# PROIECT_OPEN_READER_v57.net
KiCad netlist of a schematic drawn in EAGLE
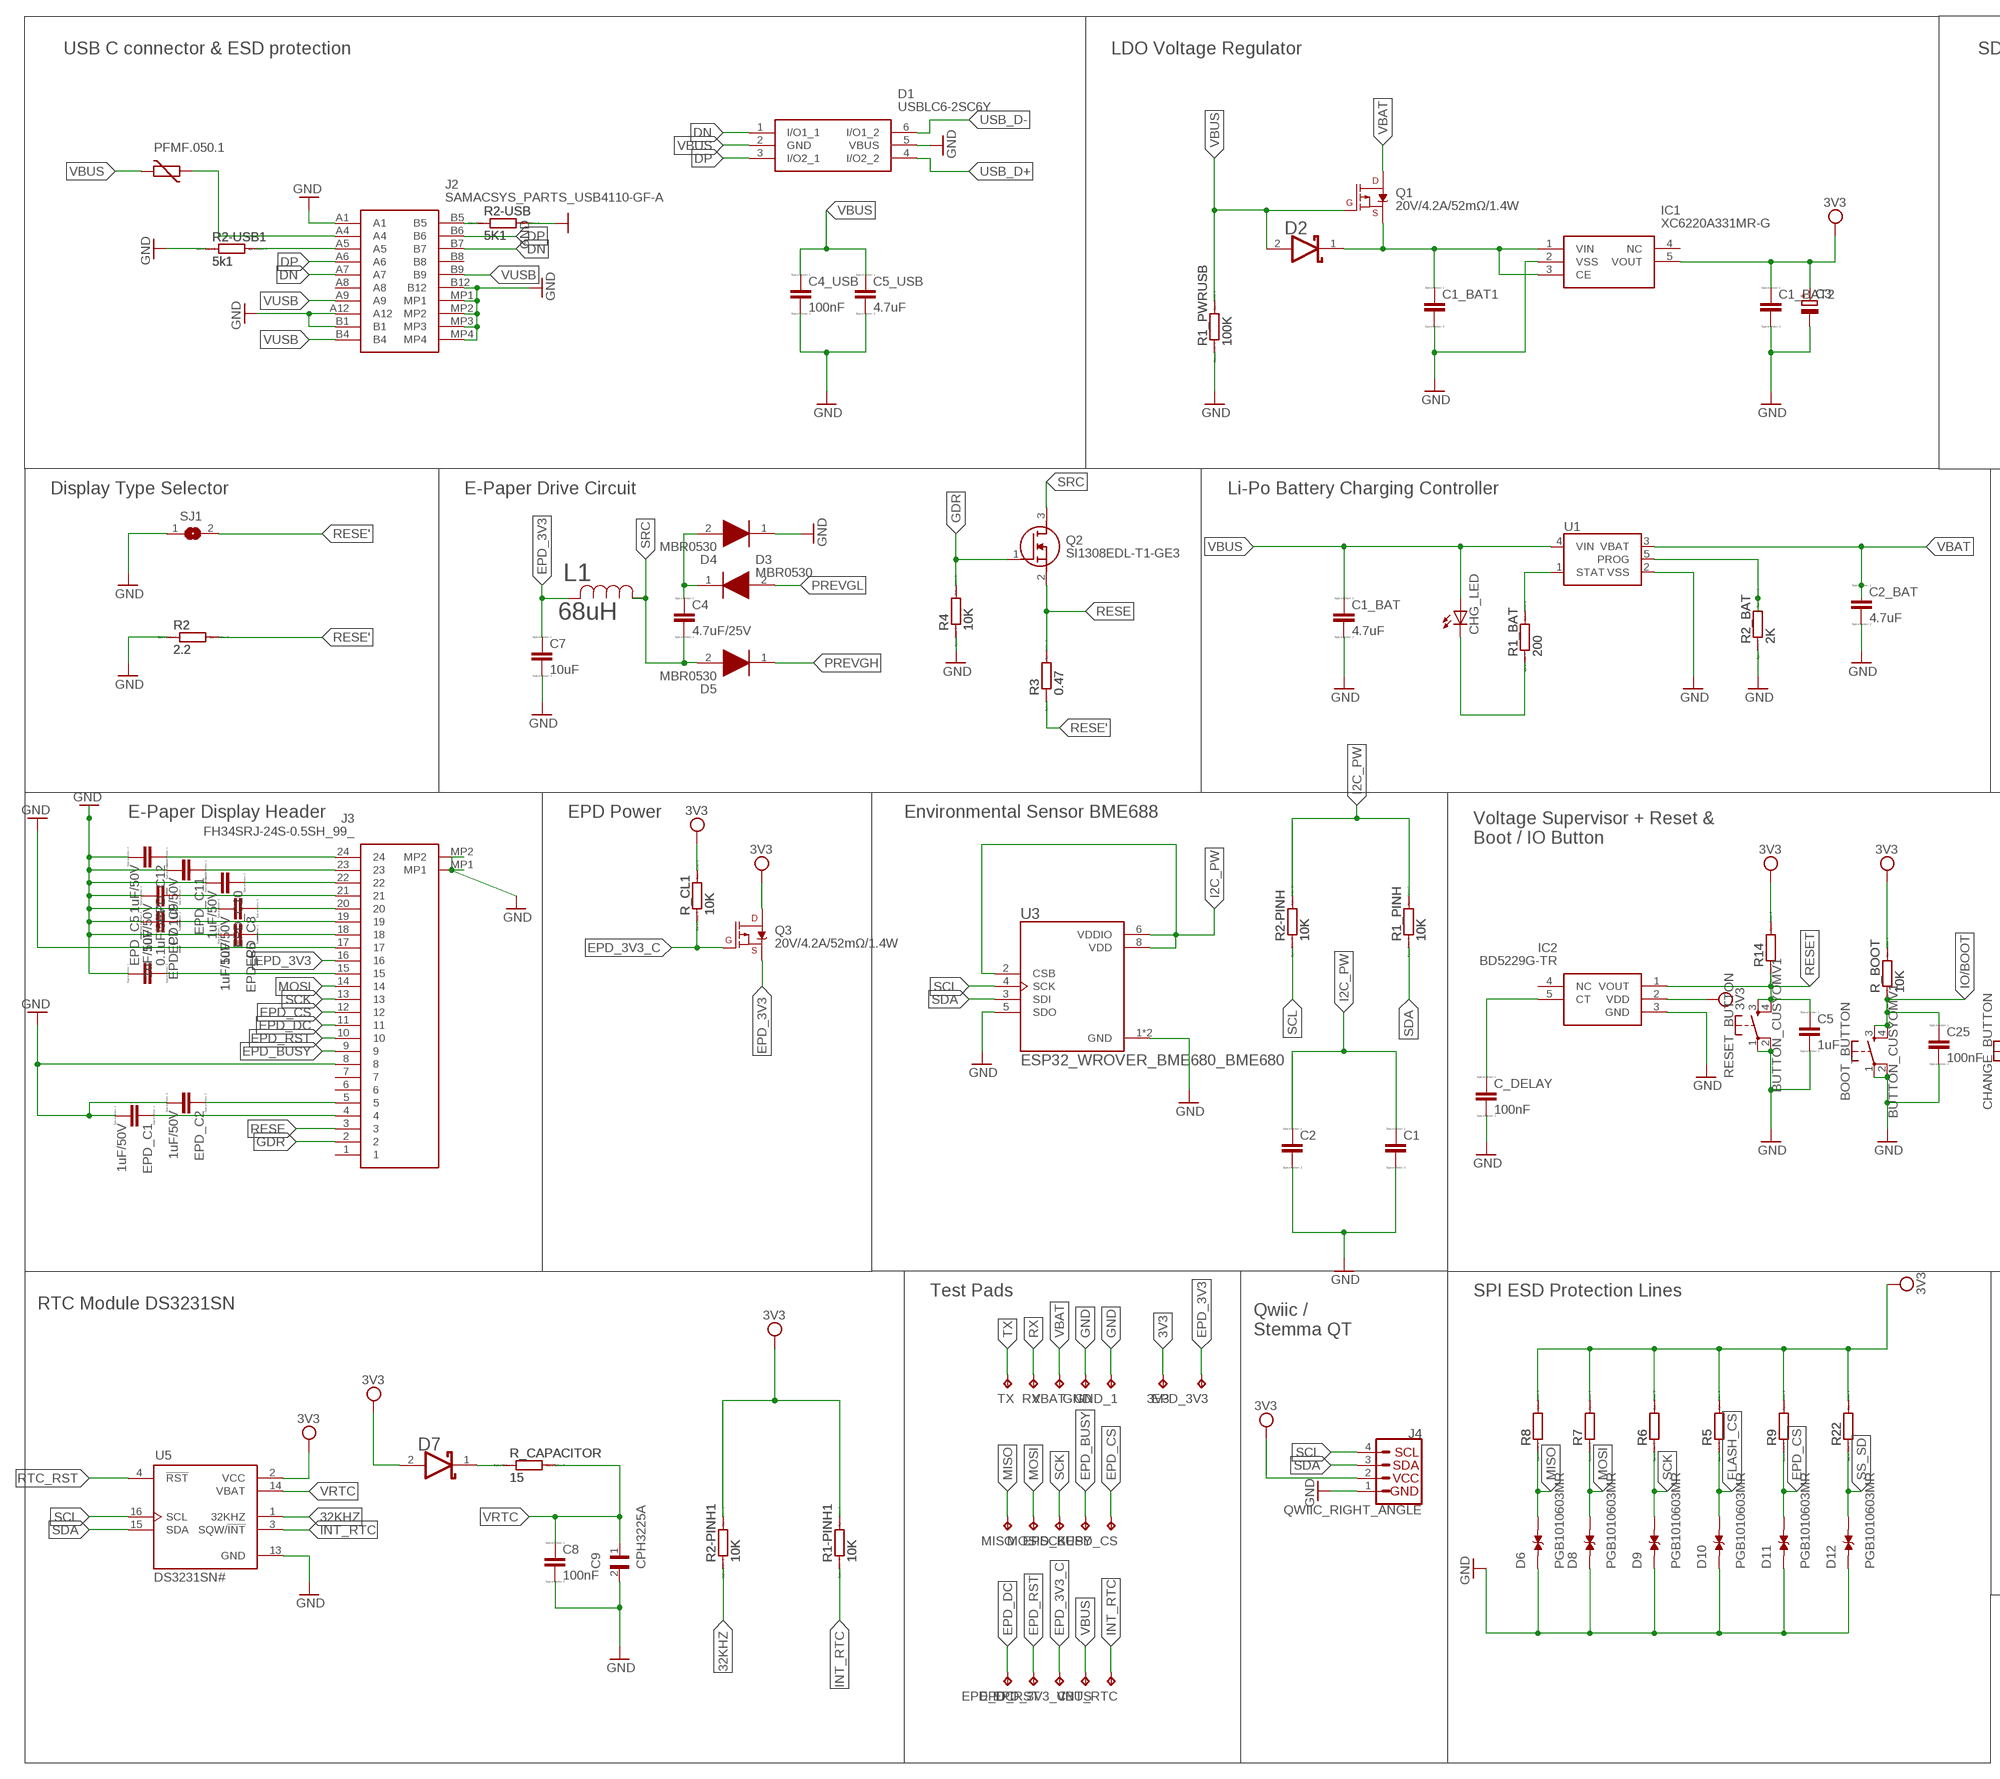
[diagram p0: schematic, sheet 1, part 1 of 2]
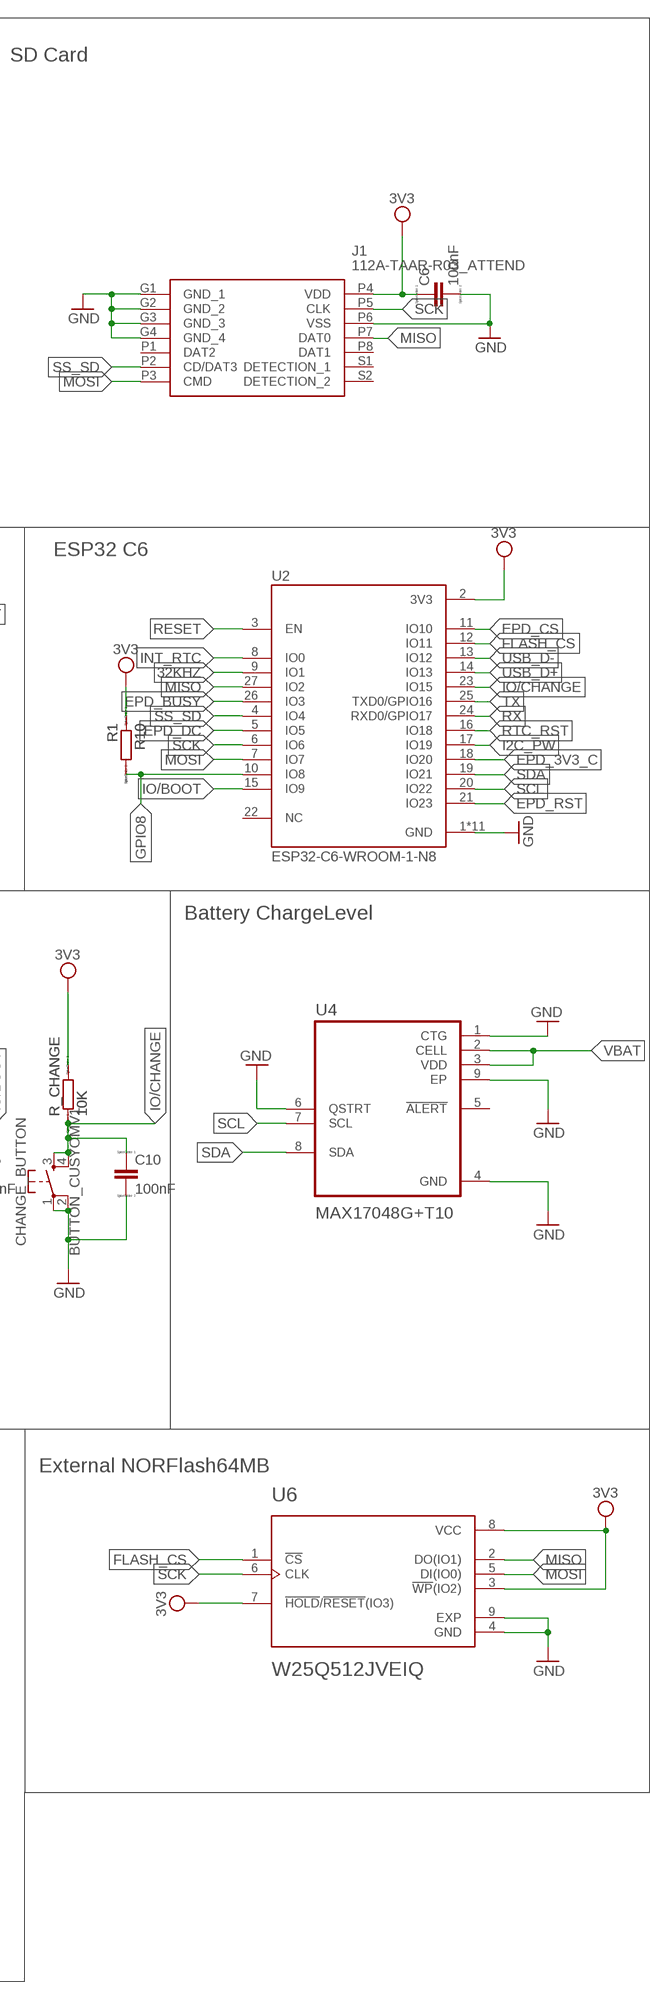
[diagram p1: schematic, sheet 1, part 2 of 2]

(export (version "E")
  (design (tool "Eeschema 10.0.6"))
  (components
    (comp (ref "3V3")
      (value "TPTP20R")
      (footprint "eagle-import:TP20R")
      (libsource (lib "eagle-import") (part "TPTP20R"))
    )
    (comp (ref "BOOT_BUTTON")
      (value "BUTTON_CUSYOMV1")
      (footprint "eagle-import:MYBUTTON")
      (libsource (lib "eagle-import") (part "BUTTON_CUSYOMV1"))
    )
    (comp (ref "C1")
      (value "EAGLE-LTSPICE_CC0402")
      (footprint "eagle-import:EAGLE-LTSPICE_C0402")
      (libsource (lib "eagle-import") (part "EAGLE-LTSPICE_CC0402"))
    )
    (comp (ref "C1_BAT")
      (value "4.7uF")
      (footprint "eagle-import:EAGLE-LTSPICE_C0402")
      (libsource (lib "eagle-import") (part "EAGLE-LTSPICE_CC0402"))
    )
    (comp (ref "C1_BAT1")
      (value "EAGLE-LTSPICE_CC0402")
      (footprint "eagle-import:EAGLE-LTSPICE_C0402")
      (libsource (lib "eagle-import") (part "EAGLE-LTSPICE_CC0402"))
    )
    (comp (ref "C1_BAT2")
      (value "EAGLE-LTSPICE_CC0402")
      (footprint "eagle-import:EAGLE-LTSPICE_C0402")
      (libsource (lib "eagle-import") (part "EAGLE-LTSPICE_CC0402"))
    )
    (comp (ref "C2")
      (value "EAGLE-LTSPICE_CC0402")
      (footprint "eagle-import:EAGLE-LTSPICE_C0402")
      (libsource (lib "eagle-import") (part "EAGLE-LTSPICE_CC0402"))
    )
    (comp (ref "C2_BAT")
      (value "4.7uF")
      (footprint "eagle-import:EAGLE-LTSPICE_C0402")
      (libsource (lib "eagle-import") (part "EAGLE-LTSPICE_CC0402"))
    )
    (comp (ref "C3")
      (value "RCL_CPOL-EUCT3528")
      (footprint "eagle-import:RCL_CT3528")
      (libsource (lib "eagle-import") (part "RCL_CPOL-EUCT3528"))
    )
    (comp (ref "C4")
      (value "4.7uF/25V")
      (footprint "eagle-import:EAGLE-LTSPICE_C0402")
      (libsource (lib "eagle-import") (part "EAGLE-LTSPICE_CC0402"))
    )
    (comp (ref "C4_USB")
      (value "100nF")
      (footprint "eagle-import:EAGLE-LTSPICE_C0402")
      (libsource (lib "eagle-import") (part "EAGLE-LTSPICE_CC0402"))
    )
    (comp (ref "C5")
      (value "1uF")
      (footprint "eagle-import:EAGLE-LTSPICE_C0402")
      (libsource (lib "eagle-import") (part "EAGLE-LTSPICE_CC0402"))
    )
    (comp (ref "C5_USB")
      (value "4.7uF")
      (footprint "eagle-import:EAGLE-LTSPICE_C0402")
      (libsource (lib "eagle-import") (part "EAGLE-LTSPICE_CC0402"))
    )
    (comp (ref "C6")
      (value "100nF")
      (footprint "eagle-import:EAGLE-LTSPICE_C0402")
      (libsource (lib "eagle-import") (part "EAGLE-LTSPICE_CC0402"))
    )
    (comp (ref "C7")
      (value "10uF")
      (footprint "eagle-import:EAGLE-LTSPICE_C0402")
      (libsource (lib "eagle-import") (part "EAGLE-LTSPICE_CC0402"))
    )
    (comp (ref "C8")
      (value "100nF")
      (footprint "eagle-import:EAGLE-LTSPICE_C0402")
      (libsource (lib "eagle-import") (part "EAGLE-LTSPICE_CC0402"))
    )
    (comp (ref "C9")
      (value "CPH3225A")
      (footprint "eagle-import:CAPCP3225X100N")
      (fields (field (name "MF") "Seiko Instruments"))
      (libsource (lib "eagle-import") (part "CPH3225A"))
    )
    (comp (ref "C10")
      (value "100nF")
      (footprint "eagle-import:EAGLE-LTSPICE_C0402")
      (libsource (lib "eagle-import") (part "EAGLE-LTSPICE_CC0402"))
    )
    (comp (ref "C25")
      (value "100nF")
      (footprint "eagle-import:EAGLE-LTSPICE_C0402")
      (libsource (lib "eagle-import") (part "EAGLE-LTSPICE_CC0402"))
    )
    (comp (ref "CHANGE_BUTTON")
      (value "BUTTON_CUSYOMV1")
      (footprint "eagle-import:MYBUTTON")
      (libsource (lib "eagle-import") (part "BUTTON_CUSYOMV1"))
    )
    (comp (ref "CHG_LED")
      (value "ADAFRUIT_LEDCHIP-LED0603")
      (footprint "eagle-import:ADAFRUIT_CHIP-LED0603")
      (libsource (lib "eagle-import") (part "ADAFRUIT_LEDCHIP-LED0603"))
    )
    (comp (ref "C_DELAY")
      (value "100nF")
      (footprint "eagle-import:EAGLE-LTSPICE_C0402")
      (libsource (lib "eagle-import") (part "EAGLE-LTSPICE_CC0402"))
    )
    (comp (ref "D1")
      (value "USBLC6-2SC6Y")
      (footprint "eagle-import:SOT95P280X145-6N")
      (fields (field (name "MF") "STMicroelectronics"))
      (libsource (lib "eagle-import") (part "USBLC6-2SC6Y"))
    )
    (comp (ref "D2")
      (value "ESP32_WROVER_AVX---SD0805S020S1R0_AVX_SD0805S020S1R0_0_0AVX_SD0805S020S1R0_0_0")
      (footprint "eagle-import:ESP32_WROVER_AVX---SD0805S020S1R0_AVX_SD0805S020S1R0_0")
      (fields
        (field (name "DIGIKEY_PART_NUMBER") "478-7800-1-ND")
        (field (name "MF") "AVX")
        (field (name "MOUSER_PART_NUMBER") "581-SD0805S020S1R0")
      )
      (libsource (lib "eagle-import") (part "ESP32_WROVER_AVX---SD0805S020S1R0_AVX_SD0805S020S1R0_0_0AVX_SD0805S020S1R0_0_0"))
    )
    (comp (ref "D3")
      (value "MBR0530")
      (footprint "eagle-import:SOD3716X135N")
      (fields (field (name "MF") "ON Semiconductor"))
      (libsource (lib "eagle-import") (part "MBR0530"))
    )
    (comp (ref "D4")
      (value "MBR0530")
      (footprint "eagle-import:SOD3716X135N")
      (fields (field (name "MF") "ON Semiconductor"))
      (libsource (lib "eagle-import") (part "MBR0530"))
    )
    (comp (ref "D5")
      (value "MBR0530")
      (footprint "eagle-import:SOD3716X135N")
      (fields (field (name "MF") "ON Semiconductor"))
      (libsource (lib "eagle-import") (part "MBR0530"))
    )
    (comp (ref "D6")
      (value "PGB1010603MR")
      (footprint "eagle-import:DIOC1608X36N")
      (fields (field (name "MF") "Littelfuse Inc."))
      (libsource (lib "eagle-import") (part "PGB1010603MR"))
    )
    (comp (ref "D7")
      (value "ESP32_WROVER_AVX---SD0805S020S1R0_AVX_SD0805S020S1R0_0_0AVX_SD0805S020S1R0_0_0")
      (footprint "eagle-import:ESP32_WROVER_AVX---SD0805S020S1R0_AVX_SD0805S020S1R0_0")
      (fields
        (field (name "DIGIKEY_PART_NUMBER") "478-7800-1-ND")
        (field (name "MF") "AVX")
        (field (name "MOUSER_PART_NUMBER") "581-SD0805S020S1R0")
      )
      (libsource (lib "eagle-import") (part "ESP32_WROVER_AVX---SD0805S020S1R0_AVX_SD0805S020S1R0_0_0AVX_SD0805S020S1R0_0_0"))
    )
    (comp (ref "D8")
      (value "PGB1010603MR")
      (footprint "eagle-import:DIOC1608X36N")
      (fields (field (name "MF") "Littelfuse Inc."))
      (libsource (lib "eagle-import") (part "PGB1010603MR"))
    )
    (comp (ref "D9")
      (value "PGB1010603MR")
      (footprint "eagle-import:DIOC1608X36N")
      (fields (field (name "MF") "Littelfuse Inc."))
      (libsource (lib "eagle-import") (part "PGB1010603MR"))
    )
    (comp (ref "D10")
      (value "PGB1010603MR")
      (footprint "eagle-import:DIOC1608X36N")
      (fields (field (name "MF") "Littelfuse Inc."))
      (libsource (lib "eagle-import") (part "PGB1010603MR"))
    )
    (comp (ref "D11")
      (value "PGB1010603MR")
      (footprint "eagle-import:DIOC1608X36N")
      (fields (field (name "MF") "Littelfuse Inc."))
      (libsource (lib "eagle-import") (part "PGB1010603MR"))
    )
    (comp (ref "D12")
      (value "PGB1010603MR")
      (footprint "eagle-import:DIOC1608X36N")
      (fields (field (name "MF") "Littelfuse Inc."))
      (libsource (lib "eagle-import") (part "PGB1010603MR"))
    )
    (comp (ref "EPD_3V3")
      (value "TPTP20R")
      (footprint "eagle-import:TP20R")
      (libsource (lib "eagle-import") (part "TPTP20R"))
    )
    (comp (ref "EPD_3V3_C")
      (value "TPTP20R")
      (footprint "eagle-import:TP20R")
      (libsource (lib "eagle-import") (part "TPTP20R"))
    )
    (comp (ref "EPD_BUSY")
      (value "TPTP20R")
      (footprint "eagle-import:TP20R")
      (libsource (lib "eagle-import") (part "TPTP20R"))
    )
    (comp (ref "EPD_C1")
      (value "1uF/50V")
      (footprint "eagle-import:EAGLE-LTSPICE_C0402")
      (libsource (lib "eagle-import") (part "EAGLE-LTSPICE_CC0402"))
    )
    (comp (ref "EPD_C2")
      (value "1uF/50V")
      (footprint "eagle-import:EAGLE-LTSPICE_C0402")
      (libsource (lib "eagle-import") (part "EAGLE-LTSPICE_CC0402"))
    )
    (comp (ref "EPD_C5")
      (value "0.1uF/50V")
      (footprint "eagle-import:EAGLE-LTSPICE_C0402")
      (libsource (lib "eagle-import") (part "EAGLE-LTSPICE_CC0402"))
    )
    (comp (ref "EPD_C6")
      (value "1uF/50V")
      (footprint "eagle-import:EAGLE-LTSPICE_C0402")
      (libsource (lib "eagle-import") (part "EAGLE-LTSPICE_CC0402"))
    )
    (comp (ref "EPD_C7")
      (value "1uF/50V")
      (footprint "eagle-import:EAGLE-LTSPICE_C0402")
      (libsource (lib "eagle-import") (part "EAGLE-LTSPICE_CC0402"))
    )
    (comp (ref "EPD_C8")
      (value "1uF/50V")
      (footprint "eagle-import:EAGLE-LTSPICE_C0402")
      (libsource (lib "eagle-import") (part "EAGLE-LTSPICE_CC0402"))
    )
    (comp (ref "EPD_C9")
      (value "1uF/50V")
      (footprint "eagle-import:EAGLE-LTSPICE_C0402")
      (libsource (lib "eagle-import") (part "EAGLE-LTSPICE_CC0402"))
    )
    (comp (ref "EPD_C10")
      (value "1uF/50V")
      (footprint "eagle-import:EAGLE-LTSPICE_C0402")
      (libsource (lib "eagle-import") (part "EAGLE-LTSPICE_CC0402"))
    )
    (comp (ref "EPD_C11")
      (value "1uF/50V")
      (footprint "eagle-import:EAGLE-LTSPICE_C0402")
      (libsource (lib "eagle-import") (part "EAGLE-LTSPICE_CC0402"))
    )
    (comp (ref "EPD_C12")
      (value "1uF/50V")
      (footprint "eagle-import:EAGLE-LTSPICE_C0402")
      (libsource (lib "eagle-import") (part "EAGLE-LTSPICE_CC0402"))
    )
    (comp (ref "EPD_CS")
      (value "TPTP20R")
      (footprint "eagle-import:TP20R")
      (libsource (lib "eagle-import") (part "TPTP20R"))
    )
    (comp (ref "EPD_DC")
      (value "TPTP20R")
      (footprint "eagle-import:TP20R")
      (libsource (lib "eagle-import") (part "TPTP20R"))
    )
    (comp (ref "EPD_RST")
      (value "TPTP20R")
      (footprint "eagle-import:TP20R")
      (libsource (lib "eagle-import") (part "TPTP20R"))
    )
    (comp (ref "GND")
      (value "TPTP20R")
      (footprint "eagle-import:TP20R")
      (libsource (lib "eagle-import") (part "TPTP20R"))
    )
    (comp (ref "GND_1")
      (value "TPTP20R")
      (footprint "eagle-import:TP20R")
      (libsource (lib "eagle-import") (part "TPTP20R"))
    )
    (comp (ref "IC1")
      (value "XC6220A331MR-G")
      (footprint "eagle-import:SOT95P280X120-5N")
      (fields (field (name "MOUSER_PART_NUMBER") "865-XC6220A331MR-G"))
      (libsource (lib "eagle-import") (part "XC6220A331MR-G"))
    )
    (comp (ref "IC2")
      (value "BD5229G-TR")
      (footprint "eagle-import:SOT95P280X125-5N")
      (fields (field (name "MOUSER_PART_NUMBER") "755-BD5229G-TR"))
      (libsource (lib "eagle-import") (part "BD5229G-TR"))
    )
    (comp (ref "INT_RTC")
      (value "TPTP20R")
      (footprint "eagle-import:TP20R")
      (libsource (lib "eagle-import") (part "TPTP20R"))
    )
    (comp (ref "J1")
      (value "112A-TAAR-R03_ATTEND")
      (footprint "eagle-import:112ATAARR03ATTEND")
      (fields (field (name "MANUFACTURER_PART_NUMBER") "112A-TAAR-R03 ATTEND"))
      (libsource (lib "eagle-import") (part "112A-TAAR-R03_ATTEND"))
    )
    (comp (ref "J2")
      (value "SAMACSYS_PARTS_USB4110-GF-A")
      (footprint "eagle-import:SAMACSYS_PARTS_USB4110GFA")
      (fields
        (field (name "MANUFACTURER_PART_NUMBER") "USB4110-GF-A")
        (field (name "MOUSER_PART_NUMBER") "640-USB4110-GF-A")
      )
      (libsource (lib "eagle-import") (part "SAMACSYS_PARTS_USB4110-GF-A"))
    )
    (comp (ref "J3")
      (value "FH34SRJ-24S-0.5SH_99_")
      (footprint "eagle-import:FH34SRJ24S05SH99")
      (fields
        (field (name "MANUFACTURER_PART_NUMBER") "FH34SRJ-24S-0.5SH(99)")
        (field (name "MOUSER_PART_NUMBER") "798-FH34SRJ24S05SH99")
      )
      (libsource (lib "eagle-import") (part "FH34SRJ-24S-0.5SH_99_"))
    )
    (comp (ref "J4")
      (value "QWIIC_RIGHT_ANGLE")
      (footprint "eagle-import:JST04_1MM_RA")
      (libsource (lib "eagle-import") (part "QWIIC_CONNECTORJS-1MM"))
    )
    (comp (ref "L1")
      (value "68uH")
      (footprint "eagle-import:IND_4828-WE-TPC_WRE")
      (fields
        (field (name "MANUFACTURER_PART_NUMBER") "744043680")
        (field (name "COPYRIGHT") "Copyright (C) 2024 Ultra Librarian. All rights reserved.")
      )
      (libsource (lib "eagle-import") (part "744043680IND_4828-WE-TPC_WRE"))
    )
    (comp (ref "MISO")
      (value "TPTP20R")
      (footprint "eagle-import:TP20R")
      (libsource (lib "eagle-import") (part "TPTP20R"))
    )
    (comp (ref "MOSI")
      (value "TPTP20R")
      (footprint "eagle-import:TP20R")
      (libsource (lib "eagle-import") (part "TPTP20R"))
    )
    (comp (ref "PFMF.050.1")
      (value "ESP32C6_VARISTORCN1812")
      (footprint "eagle-import:ESP32C6_VARISTOR_CT_CN1812")
      (libsource (lib "eagle-import") (part "ESP32C6_VARISTORCN1812"))
    )
    (comp (ref "Q1")
      (value "20V/4.2A/52mΩ/1.4W")
      (footprint "eagle-import:ESP32_WROVER_SPARKFUN-DISCRETESEMI_SOT23-3")
      (libsource (lib "eagle-import") (part "ESP32_WROVER_SPARKFUN-DISCRETESEMI_MOSFET_PCH-DMG2305UX-7"))
    )
    (comp (ref "Q2")
      (value "SI1308EDL-T1-GE3")
      (footprint "eagle-import:SOT65P210X110-3N")
      (fields (field (name "MF") "Vishay Siliconix"))
      (libsource (lib "eagle-import") (part "SI1308EDL-T1-GE3"))
    )
    (comp (ref "Q3")
      (value "20V/4.2A/52mΩ/1.4W")
      (footprint "eagle-import:ESP32_WROVER_SPARKFUN-DISCRETESEMI_SOT23-3")
      (libsource (lib "eagle-import") (part "ESP32_WROVER_SPARKFUN-DISCRETESEMI_MOSFET_PCH-DMG2305UX-7"))
    )
    (comp (ref "R1-PINH1")
      (value "10K")
      (footprint "eagle-import:ESP32_WROVER_EAGLE-LTSPICE_R0402")
      (libsource (lib "eagle-import") (part "ESP32_WROVER_EAGLE-LTSPICE_RR0402"))
    )
    (comp (ref "R1_BAT")
      (value "200")
      (footprint "eagle-import:ESP32_WROVER_EAGLE-LTSPICE_R0402")
      (libsource (lib "eagle-import") (part "ESP32_WROVER_EAGLE-LTSPICE_RR0402"))
    )
    (comp (ref "R1_PINH")
      (value "10K")
      (footprint "eagle-import:ESP32_WROVER_EAGLE-LTSPICE_R0402")
      (libsource (lib "eagle-import") (part "ESP32_WROVER_EAGLE-LTSPICE_RR0402"))
    )
    (comp (ref "R1_PWRUSB")
      (value "100K")
      (footprint "eagle-import:ESP32_WROVER_EAGLE-LTSPICE_R0402")
      (libsource (lib "eagle-import") (part "ESP32_WROVER_EAGLE-LTSPICE_RR0402"))
    )
    (comp (ref "R2")
      (value "2.2")
      (footprint "eagle-import:ESP32_WROVER_EAGLE-LTSPICE_R0402")
      (libsource (lib "eagle-import") (part "ESP32_WROVER_EAGLE-LTSPICE_RR0402"))
    )
    (comp (ref "R2-PINH")
      (value "10K")
      (footprint "eagle-import:ESP32_WROVER_EAGLE-LTSPICE_R0402")
      (libsource (lib "eagle-import") (part "ESP32_WROVER_EAGLE-LTSPICE_RR0402"))
    )
    (comp (ref "R2-PINH1")
      (value "10K")
      (footprint "eagle-import:ESP32_WROVER_EAGLE-LTSPICE_R0402")
      (libsource (lib "eagle-import") (part "ESP32_WROVER_EAGLE-LTSPICE_RR0402"))
    )
    (comp (ref "R2-USB")
      (value "5K1")
      (footprint "eagle-import:ESP32_WROVER_EAGLE-LTSPICE_R0402")
      (libsource (lib "eagle-import") (part "ESP32_WROVER_EAGLE-LTSPICE_RR0402"))
    )
    (comp (ref "R2-USB1")
      (value "5k1")
      (footprint "eagle-import:ESP32_WROVER_EAGLE-LTSPICE_R0402")
      (libsource (lib "eagle-import") (part "ESP32_WROVER_EAGLE-LTSPICE_RR0402"))
    )
    (comp (ref "R2_BAT")
      (value "2K")
      (footprint "eagle-import:ESP32_WROVER_EAGLE-LTSPICE_R0402")
      (libsource (lib "eagle-import") (part "ESP32_WROVER_EAGLE-LTSPICE_RR0402"))
    )
    (comp (ref "R3")
      (value "0.47")
      (footprint "eagle-import:ESP32_WROVER_EAGLE-LTSPICE_R0402")
      (libsource (lib "eagle-import") (part "ESP32_WROVER_EAGLE-LTSPICE_RR0402"))
    )
    (comp (ref "R4")
      (value "10K")
      (footprint "eagle-import:ESP32_WROVER_EAGLE-LTSPICE_R0402")
      (libsource (lib "eagle-import") (part "ESP32_WROVER_EAGLE-LTSPICE_RR0402"))
    )
    (comp (ref "R5")
      (value "ESP32_WROVER_EAGLE-LTSPICE_RR0402")
      (footprint "eagle-import:ESP32_WROVER_EAGLE-LTSPICE_R0402")
      (libsource (lib "eagle-import") (part "ESP32_WROVER_EAGLE-LTSPICE_RR0402"))
    )
    (comp (ref "R6")
      (value "ESP32_WROVER_EAGLE-LTSPICE_RR0402")
      (footprint "eagle-import:ESP32_WROVER_EAGLE-LTSPICE_R0402")
      (libsource (lib "eagle-import") (part "ESP32_WROVER_EAGLE-LTSPICE_RR0402"))
    )
    (comp (ref "R7")
      (value "ESP32_WROVER_EAGLE-LTSPICE_RR0402")
      (footprint "eagle-import:ESP32_WROVER_EAGLE-LTSPICE_R0402")
      (libsource (lib "eagle-import") (part "ESP32_WROVER_EAGLE-LTSPICE_RR0402"))
    )
    (comp (ref "R8")
      (value "ESP32_WROVER_EAGLE-LTSPICE_RR0402")
      (footprint "eagle-import:ESP32_WROVER_EAGLE-LTSPICE_R0402")
      (libsource (lib "eagle-import") (part "ESP32_WROVER_EAGLE-LTSPICE_RR0402"))
    )
    (comp (ref "R9")
      (value "ESP32_WROVER_EAGLE-LTSPICE_RR0402")
      (footprint "eagle-import:ESP32_WROVER_EAGLE-LTSPICE_R0402")
      (libsource (lib "eagle-import") (part "ESP32_WROVER_EAGLE-LTSPICE_RR0402"))
    )
    (comp (ref "R10")
      (value "R1")
      (footprint "eagle-import:ESP32_WROVER_EAGLE-LTSPICE_R0402")
      (libsource (lib "eagle-import") (part "ESP32_WROVER_EAGLE-LTSPICE_RR0402"))
    )
    (comp (ref "R14")
      (value "ESP32_WROVER_EAGLE-LTSPICE_RR0402")
      (footprint "eagle-import:ESP32_WROVER_EAGLE-LTSPICE_R0402")
      (libsource (lib "eagle-import") (part "ESP32_WROVER_EAGLE-LTSPICE_RR0402"))
    )
    (comp (ref "R22")
      (value "ESP32_WROVER_EAGLE-LTSPICE_RR0402")
      (footprint "eagle-import:ESP32_WROVER_EAGLE-LTSPICE_R0402")
      (libsource (lib "eagle-import") (part "ESP32_WROVER_EAGLE-LTSPICE_RR0402"))
    )
    (comp (ref "RESET_BUTTON")
      (value "BUTTON_CUSYOMV1")
      (footprint "eagle-import:MYBUTTON")
      (libsource (lib "eagle-import") (part "BUTTON_CUSYOMV1"))
    )
    (comp (ref "RX")
      (value "TPTP20R")
      (footprint "eagle-import:TP20R")
      (libsource (lib "eagle-import") (part "TPTP20R"))
    )
    (comp (ref "R_BOOT")
      (value "10K")
      (footprint "eagle-import:ESP32_WROVER_EAGLE-LTSPICE_R0402")
      (libsource (lib "eagle-import") (part "ESP32_WROVER_EAGLE-LTSPICE_RR0402"))
    )
    (comp (ref "R_CAPACITOR")
      (value "15")
      (footprint "eagle-import:ESP32_WROVER_EAGLE-LTSPICE_R0402")
      (libsource (lib "eagle-import") (part "ESP32_WROVER_EAGLE-LTSPICE_RR0402"))
    )
    (comp (ref "R_CHANGE")
      (value "10K")
      (footprint "eagle-import:ESP32_WROVER_EAGLE-LTSPICE_R0402")
      (libsource (lib "eagle-import") (part "ESP32_WROVER_EAGLE-LTSPICE_RR0402"))
    )
    (comp (ref "R_CL1")
      (value "10K")
      (footprint "eagle-import:ESP32_WROVER_EAGLE-LTSPICE_R0402")
      (libsource (lib "eagle-import") (part "ESP32_WROVER_EAGLE-LTSPICE_RR0402"))
    )
    (comp (ref "SCK")
      (value "TPTP20R")
      (footprint "eagle-import:TP20R")
      (libsource (lib "eagle-import") (part "TPTP20R"))
    )
    (comp (ref "SJ1") (value "SJ") (footprint "eagle-import:SJ") (libsource (lib "eagle-import") (part "SJ")))
    (comp (ref "TX")
      (value "TPTP20R")
      (footprint "eagle-import:TP20R")
      (libsource (lib "eagle-import") (part "TPTP20R"))
    )
    (comp (ref "U1")
      (value "ESP32_WROVER_SPARKFUN-IC-POWER_MCP73831")
      (footprint "eagle-import:ESP32_WROVER_SPARKFUN-IC-POWER_SOT23-5")
      (libsource (lib "eagle-import") (part "ESP32_WROVER_SPARKFUN-IC-POWER_MCP73831"))
    )
    (comp (ref "U2")
      (value "ESP32-C6-WROOM-1-N8")
      (footprint "eagle-import:XCVR_ESP32-C6-WROOM-1-N8")
      (fields (field (name "MF") "Espressif Systems"))
      (libsource (lib "eagle-import") (part "ESP32-C6-WROOM-1-N8"))
    )
    (comp (ref "U3")
      (value "ESP32_WROVER_BME680_BME680")
      (footprint "eagle-import:ESP32_WROVER_BME680_PSON80P300X300X100-8N")
      (fields (field (name "MF") "Bosch Sensortec") (field (name "MP") "BME680"))
      (libsource (lib "eagle-import") (part "ESP32_WROVER_BME680_BME680"))
    )
    (comp (ref "U4")
      (value "MAX17048G+T10")
      (footprint "eagle-import:SON50P200X200X80-9N")
      (fields (field (name "MF") "Analog Devices"))
      (libsource (lib "eagle-import") (part "MAX17048G+T10"))
    )
    (comp (ref "U5")
      (value "DS3231SN#")
      (footprint "eagle-import:SOIC127P1032X265-16N")
      (fields (field (name "MF") "Analog Devices"))
      (libsource (lib "eagle-import") (part "DS3231SN#"))
    )
    (comp (ref "U6")
      (value "W25Q512JVEIQ")
      (footprint "eagle-import:SON127P600X800X80-9N")
      (fields (field (name "MF") "Winbond Electronics"))
      (libsource (lib "eagle-import") (part "W25Q512JVEIQ"))
    )
    (comp (ref "VBAT")
      (value "TPTP20R")
      (footprint "eagle-import:TP20R")
      (libsource (lib "eagle-import") (part "TPTP20R"))
    )
    (comp (ref "VBUS")
      (value "TPTP20R")
      (footprint "eagle-import:TP20R")
      (libsource (lib "eagle-import") (part "TPTP20R"))
    )
  )
  (nets
    (net (code "1") (name "3V3") (class "Default")
      (node (ref "3V3") (pin "TP") (pinfunction "TP_TP") (pintype "input"))
      (node (ref "C1_BAT2") (pin "1") (pinfunction "1_1") (pintype "passive"))
      (node (ref "C3") (pin "+") (pinfunction "+_+") (pintype "passive"))
      (node (ref "C6") (pin "1") (pinfunction "1_1") (pintype "passive"))
      (node (ref "D7") (pin "2") (pinfunction "ANODE_2") (pintype "bidirectional"))
      (node (ref "IC1") (pin "5") (pinfunction "VOUT_5") (pintype "bidirectional"))
      (node (ref "IC2") (pin "2") (pinfunction "VDD_2") (pintype "bidirectional"))
      (node (ref "J1") (pin "P4") (pinfunction "VDD_P4") (pintype "bidirectional"))
      (node (ref "J4") (pin "2") (pinfunction "2_2") (pintype "power_in"))
      (node (ref "Q3") (pin "3") (pinfunction "D_3") (pintype "bidirectional"))
      (node (ref "R1-PINH1") (pin "2") (pinfunction "2_2") (pintype "passive"))
      (node (ref "R10") (pin "1") (pinfunction "1_1") (pintype "passive"))
      (node (ref "R14") (pin "2") (pinfunction "2_2") (pintype "passive"))
      (node (ref "R2-PINH1") (pin "2") (pinfunction "2_2") (pintype "passive"))
      (node (ref "R22") (pin "2") (pinfunction "2_2") (pintype "passive"))
      (node (ref "R5") (pin "2") (pinfunction "2_2") (pintype "passive"))
      (node (ref "R6") (pin "2") (pinfunction "2_2") (pintype "passive"))
      (node (ref "R7") (pin "2") (pinfunction "2_2") (pintype "passive"))
      (node (ref "R8") (pin "2") (pinfunction "2_2") (pintype "passive"))
      (node (ref "R9") (pin "2") (pinfunction "2_2") (pintype "passive"))
      (node (ref "R_BOOT") (pin "2") (pinfunction "2_2") (pintype "passive"))
      (node (ref "R_CHANGE") (pin "2") (pinfunction "2_2") (pintype "passive"))
      (node (ref "R_CL1") (pin "2") (pinfunction "2_2") (pintype "passive"))
      (node (ref "U2") (pin "2") (pinfunction "3V3_2") (pintype "power_in"))
      (node (ref "U5") (pin "2") (pinfunction "VCC_2") (pintype "power_in"))
      (node (ref "U6") (pin "3") (pinfunction "~{WP}(IO2)_3") (pintype "bidirectional"))
      (node (ref "U6") (pin "7") (pinfunction "~{HOLD}/~{RESET}(IO3)_7") (pintype "bidirectional"))
      (node (ref "U6") (pin "8") (pinfunction "VCC_8") (pintype "power_in"))
    )
    (net (code "2") (name "32KHZ") (class "Default")
      (node (ref "R2-PINH1") (pin "1") (pinfunction "1_1") (pintype "passive"))
      (node (ref "U2") (pin "9") (pinfunction "IO1_9") (pintype "bidirectional"))
      (node (ref "U5") (pin "1") (pinfunction "32KHZ_1") (pintype "output"))
    )
    (net (code "3") (name "DN") (class "Default")
      (node (ref "D1") (pin "1") (pinfunction "I/O1_1_1") (pintype "bidirectional"))
      (node (ref "J2") (pin "A7") (pinfunction "A7_A7") (pintype "bidirectional"))
      (node (ref "J2") (pin "B7") (pinfunction "B7_B7") (pintype "bidirectional"))
    )
    (net (code "4") (name "DP") (class "Default")
      (node (ref "D1") (pin "3") (pinfunction "I/O2_1_3") (pintype "bidirectional"))
      (node (ref "J2") (pin "A6") (pinfunction "A6_A6") (pintype "bidirectional"))
      (node (ref "J2") (pin "B6") (pinfunction "B6_B6") (pintype "bidirectional"))
    )
    (net (code "5") (name "EPD_3V3") (class "Default")
      (node (ref "C7") (pin "1") (pinfunction "1_1") (pintype "passive"))
      (node (ref "EPD_3V3") (pin "TP") (pinfunction "TP_TP") (pintype "input"))
      (node (ref "J3") (pin "16") (pinfunction "16_16") (pintype "bidirectional"))
      (node (ref "L1") (pin "2") (pinfunction "2_2") (pintype "passive"))
      (node (ref "Q3") (pin "2") (pinfunction "S_2") (pintype "bidirectional"))
    )
    (net (code "6") (name "EPD_3V3_C") (class "Default")
      (node (ref "EPD_3V3_C") (pin "TP") (pinfunction "TP_TP") (pintype "input"))
      (node (ref "Q3") (pin "1") (pinfunction "G_1") (pintype "bidirectional"))
      (node (ref "R_CL1") (pin "1") (pinfunction "1_1") (pintype "passive"))
      (node (ref "U2") (pin "18") (pinfunction "IO20_18") (pintype "bidirectional"))
    )
    (net (code "7") (name "EPD_BUSY") (class "Default")
      (node (ref "EPD_BUSY") (pin "TP") (pinfunction "TP_TP") (pintype "input"))
      (node (ref "J3") (pin "9") (pinfunction "9_9") (pintype "bidirectional"))
      (node (ref "U2") (pin "26") (pinfunction "IO3_26") (pintype "bidirectional"))
    )
    (net (code "8") (name "EPD_CS") (class "Default")
      (node (ref "D11") (pin "2") (pinfunction "2_2") (pintype "passive"))
      (node (ref "EPD_CS") (pin "TP") (pinfunction "TP_TP") (pintype "input"))
      (node (ref "J3") (pin "12") (pinfunction "12_12") (pintype "bidirectional"))
      (node (ref "R9") (pin "1") (pinfunction "1_1") (pintype "passive"))
      (node (ref "U2") (pin "11") (pinfunction "IO10_11") (pintype "bidirectional"))
    )
    (net (code "9") (name "EPD_DC") (class "Default")
      (node (ref "EPD_DC") (pin "TP") (pinfunction "TP_TP") (pintype "input"))
      (node (ref "J3") (pin "11") (pinfunction "11_11") (pintype "bidirectional"))
      (node (ref "U2") (pin "5") (pinfunction "IO5_5") (pintype "bidirectional"))
    )
    (net (code "10") (name "EPD_RST") (class "Default")
      (node (ref "EPD_RST") (pin "TP") (pinfunction "TP_TP") (pintype "input"))
      (node (ref "J3") (pin "10") (pinfunction "10_10") (pintype "bidirectional"))
      (node (ref "U2") (pin "21") (pinfunction "IO23_21") (pintype "bidirectional"))
    )
    (net (code "11") (name "FLASH_CS") (class "Default")
      (node (ref "D10") (pin "2") (pinfunction "2_2") (pintype "passive"))
      (node (ref "R5") (pin "1") (pinfunction "1_1") (pintype "passive"))
      (node (ref "U2") (pin "12") (pinfunction "IO11_12") (pintype "bidirectional"))
      (node (ref "U6") (pin "1") (pinfunction "~{CS}_1") (pintype "input"))
    )
    (net (code "12") (name "GDR") (class "Default")
      (node (ref "J3") (pin "2") (pinfunction "2_2") (pintype "bidirectional"))
      (node (ref "Q2") (pin "1") (pinfunction "G_1") (pintype "bidirectional"))
      (node (ref "R4") (pin "2") (pinfunction "2_2") (pintype "passive"))
    )
    (net (code "13") (name "GND") (class "Default")
      (node (ref "BOOT_BUTTON") (pin "1") (pinfunction "1_1") (pintype "passive"))
      (node (ref "BOOT_BUTTON") (pin "2") (pinfunction "2_2") (pintype "passive"))
      (node (ref "C1") (pin "2") (pinfunction "2_2") (pintype "passive"))
      (node (ref "C10") (pin "2") (pinfunction "2_2") (pintype "passive"))
      (node (ref "C1_BAT") (pin "2") (pinfunction "2_2") (pintype "passive"))
      (node (ref "C1_BAT1") (pin "2") (pinfunction "2_2") (pintype "passive"))
      (node (ref "C1_BAT2") (pin "2") (pinfunction "2_2") (pintype "passive"))
      (node (ref "C2") (pin "2") (pinfunction "2_2") (pintype "passive"))
      (node (ref "C25") (pin "2") (pinfunction "2_2") (pintype "passive"))
      (node (ref "C2_BAT") (pin "2") (pinfunction "2_2") (pintype "passive"))
      (node (ref "C3") (pin "-") (pinfunction "-_-") (pintype "passive"))
      (node (ref "C4_USB") (pin "2") (pinfunction "2_2") (pintype "passive"))
      (node (ref "C5") (pin "2") (pinfunction "2_2") (pintype "passive"))
      (node (ref "C5_USB") (pin "2") (pinfunction "2_2") (pintype "passive"))
      (node (ref "C6") (pin "2") (pinfunction "2_2") (pintype "passive"))
      (node (ref "C7") (pin "2") (pinfunction "2_2") (pintype "passive"))
      (node (ref "C8") (pin "2") (pinfunction "2_2") (pintype "passive"))
      (node (ref "C9") (pin "2") (pinfunction "2_2") (pintype "passive"))
      (node (ref "CHANGE_BUTTON") (pin "1") (pinfunction "1_1") (pintype "passive"))
      (node (ref "CHANGE_BUTTON") (pin "2") (pinfunction "2_2") (pintype "passive"))
      (node (ref "C_DELAY") (pin "2") (pinfunction "2_2") (pintype "passive"))
      (node (ref "D1") (pin "5") (pinfunction "VBUS_5") (pintype "bidirectional"))
      (node (ref "D10") (pin "1") (pinfunction "1_1") (pintype "passive"))
      (node (ref "D11") (pin "1") (pinfunction "1_1") (pintype "passive"))
      (node (ref "D12") (pin "1") (pinfunction "1_1") (pintype "passive"))
      (node (ref "D4") (pin "1") (pinfunction "K_1") (pintype "bidirectional"))
      (node (ref "D6") (pin "1") (pinfunction "1_1") (pintype "passive"))
      (node (ref "D8") (pin "1") (pinfunction "1_1") (pintype "passive"))
      (node (ref "D9") (pin "1") (pinfunction "1_1") (pintype "passive"))
      (node (ref "EPD_C1") (pin "2") (pinfunction "2_2") (pintype "passive"))
      (node (ref "EPD_C10") (pin "2") (pinfunction "2_2") (pintype "passive"))
      (node (ref "EPD_C11") (pin "2") (pinfunction "2_2") (pintype "passive"))
      (node (ref "EPD_C12") (pin "2") (pinfunction "2_2") (pintype "passive"))
      (node (ref "EPD_C2") (pin "2") (pinfunction "2_2") (pintype "passive"))
      (node (ref "EPD_C5") (pin "1") (pinfunction "1_1") (pintype "passive"))
      (node (ref "EPD_C6") (pin "2") (pinfunction "2_2") (pintype "passive"))
      (node (ref "EPD_C7") (pin "2") (pinfunction "2_2") (pintype "passive"))
      (node (ref "EPD_C8") (pin "2") (pinfunction "2_2") (pintype "passive"))
      (node (ref "EPD_C9") (pin "2") (pinfunction "2_2") (pintype "passive"))
      (node (ref "GND") (pin "TP") (pinfunction "TP_TP") (pintype "input"))
      (node (ref "GND_1") (pin "TP") (pinfunction "TP_TP") (pintype "input"))
      (node (ref "IC1") (pin "2") (pinfunction "VSS_2") (pintype "bidirectional"))
      (node (ref "IC2") (pin "3") (pinfunction "GND_3") (pintype "bidirectional"))
      (node (ref "J1") (pin "G1") (pinfunction "GND_1_G1") (pintype "bidirectional"))
      (node (ref "J1") (pin "G2") (pinfunction "GND_2_G2") (pintype "bidirectional"))
      (node (ref "J1") (pin "G3") (pinfunction "GND_3_G3") (pintype "bidirectional"))
      (node (ref "J1") (pin "G4") (pinfunction "GND_4_G4") (pintype "bidirectional"))
      (node (ref "J1") (pin "P6") (pinfunction "VSS_P6") (pintype "bidirectional"))
      (node (ref "J2") (pin "A1") (pinfunction "A1_A1") (pintype "bidirectional"))
      (node (ref "J2") (pin "A12") (pinfunction "A12_A12") (pintype "bidirectional"))
      (node (ref "J2") (pin "B1") (pinfunction "B1_B1") (pintype "bidirectional"))
      (node (ref "J2") (pin "B12") (pinfunction "B12_B12") (pintype "bidirectional"))
      (node (ref "J2") (pin "MP1") (pinfunction "MP1_MP1") (pintype "bidirectional"))
      (node (ref "J2") (pin "MP2") (pinfunction "MP2_MP2") (pintype "bidirectional"))
      (node (ref "J2") (pin "MP3") (pinfunction "MP3_MP3") (pintype "bidirectional"))
      (node (ref "J2") (pin "MP4") (pinfunction "MP4_MP4") (pintype "bidirectional"))
      (node (ref "J3") (pin "17") (pinfunction "17_17") (pintype "bidirectional"))
      (node (ref "J3") (pin "8") (pinfunction "8_8") (pintype "bidirectional"))
      (node (ref "J3") (pin "MP1") (pinfunction "MP1_MP1") (pintype "bidirectional"))
      (node (ref "J3") (pin "MP2") (pinfunction "MP2_MP2") (pintype "bidirectional"))
      (node (ref "J4") (pin "1") (pinfunction "1_1") (pintype "power_in"))
      (node (ref "R1_PWRUSB") (pin "1") (pinfunction "1_1") (pintype "passive"))
      (node (ref "R2") (pin "1") (pinfunction "1_1") (pintype "passive"))
      (node (ref "R2-USB") (pin "2") (pinfunction "2_2") (pintype "passive"))
      (node (ref "R2-USB1") (pin "1") (pinfunction "1_1") (pintype "passive"))
      (node (ref "R2_BAT") (pin "1") (pinfunction "1_1") (pintype "passive"))
      (node (ref "R4") (pin "1") (pinfunction "1_1") (pintype "passive"))
      (node (ref "RESET_BUTTON") (pin "1") (pinfunction "1_1") (pintype "passive"))
      (node (ref "RESET_BUTTON") (pin "2") (pinfunction "2_2") (pintype "passive"))
      (node (ref "SJ1") (pin "1") (pinfunction "1_1") (pintype "passive"))
      (node (ref "U1") (pin "2") (pinfunction "VSS_2") (pintype "power_in"))
      (node (ref "U2") (pin "1") (pinfunction "GND_1") (pintype "power_in"))
      (node (ref "U2") (pin "28") (pinfunction "GND_28") (pintype "power_in"))
      (node (ref "U2") (pin "29_1") (pinfunction "GND_29_1") (pintype "power_in"))
      (node (ref "U2") (pin "29_2") (pinfunction "GND_29_2") (pintype "power_in"))
      (node (ref "U2") (pin "29_3") (pinfunction "GND_29_3") (pintype "power_in"))
      (node (ref "U2") (pin "29_4") (pinfunction "GND_29_4") (pintype "power_in"))
      (node (ref "U2") (pin "29_5") (pinfunction "GND_29_5") (pintype "power_in"))
      (node (ref "U2") (pin "29_6") (pinfunction "GND_29_6") (pintype "power_in"))
      (node (ref "U2") (pin "29_7") (pinfunction "GND_29_7") (pintype "power_in"))
      (node (ref "U2") (pin "29_8") (pinfunction "GND_29_8") (pintype "power_in"))
      (node (ref "U2") (pin "29_9") (pinfunction "GND_29_9") (pintype "power_in"))
      (node (ref "U3") (pin "1") (pinfunction "GND_1") (pintype "power_in"))
      (node (ref "U3") (pin "5") (pinfunction "SDO_5") (pintype "bidirectional"))
      (node (ref "U3") (pin "7") (pinfunction "GND_7") (pintype "power_in"))
      (node (ref "U4") (pin "1") (pinfunction "CTG_1") (pintype "power_in"))
      (node (ref "U4") (pin "4") (pinfunction "GND_4") (pintype "power_in"))
      (node (ref "U4") (pin "6") (pinfunction "QSTRT_6") (pintype "input"))
      (node (ref "U4") (pin "9") (pinfunction "EP_9") (pintype "power_in"))
      (node (ref "U5") (pin "13") (pinfunction "GND_13") (pintype "power_in"))
      (node (ref "U6") (pin "4") (pinfunction "GND_4") (pintype "power_in"))
      (node (ref "U6") (pin "9") (pinfunction "EXP_9") (pintype "passive"))
    )
    (net (code "14") (name "GPIO8") (class "Default")
      (node (ref "R10") (pin "2") (pinfunction "2_2") (pintype "passive"))
      (node (ref "U2") (pin "10") (pinfunction "IO8_10") (pintype "bidirectional"))
    )
    (net (code "15") (name "I2C_PW") (class "Default")
      (node (ref "C1") (pin "1") (pinfunction "1_1") (pintype "passive"))
      (node (ref "C2") (pin "1") (pinfunction "1_1") (pintype "passive"))
      (node (ref "R1_PINH") (pin "2") (pinfunction "2_2") (pintype "passive"))
      (node (ref "R2-PINH") (pin "2") (pinfunction "2_2") (pintype "passive"))
      (node (ref "U2") (pin "17") (pinfunction "IO19_17") (pintype "bidirectional"))
      (node (ref "U3") (pin "2") (pinfunction "CSB_2") (pintype "input"))
      (node (ref "U3") (pin "6") (pinfunction "VDDIO_6") (pintype "power_in"))
      (node (ref "U3") (pin "8") (pinfunction "VDD_8") (pintype "power_in"))
    )
    (net (code "16") (name "INT_RTC") (class "Default")
      (node (ref "INT_RTC") (pin "TP") (pinfunction "TP_TP") (pintype "input"))
      (node (ref "R1-PINH1") (pin "1") (pinfunction "1_1") (pintype "passive"))
      (node (ref "U2") (pin "8") (pinfunction "IO0_8") (pintype "bidirectional"))
      (node (ref "U5") (pin "3") (pinfunction "SQW/~{INT}_3") (pintype "output"))
    )
    (net (code "17") (name "IO{slash}BOOT") (class "Default")
      (node (ref "BOOT_BUTTON") (pin "3") (pinfunction "3_3") (pintype "passive"))
      (node (ref "BOOT_BUTTON") (pin "4") (pinfunction "4_4") (pintype "passive"))
      (node (ref "C25") (pin "1") (pinfunction "1_1") (pintype "passive"))
      (node (ref "R_BOOT") (pin "1") (pinfunction "1_1") (pintype "passive"))
      (node (ref "U2") (pin "15") (pinfunction "IO9_15") (pintype "bidirectional"))
    )
    (net (code "18") (name "IO{slash}CHANGE") (class "Default")
      (node (ref "C10") (pin "1") (pinfunction "1_1") (pintype "passive"))
      (node (ref "CHANGE_BUTTON") (pin "3") (pinfunction "3_3") (pintype "passive"))
      (node (ref "CHANGE_BUTTON") (pin "4") (pinfunction "4_4") (pintype "passive"))
      (node (ref "R_CHANGE") (pin "1") (pinfunction "1_1") (pintype "passive"))
      (node (ref "U2") (pin "23") (pinfunction "IO15_23") (pintype "bidirectional"))
    )
    (net (code "19") (name "MISO") (class "Default")
      (node (ref "D6") (pin "2") (pinfunction "2_2") (pintype "passive"))
      (node (ref "J1") (pin "P7") (pinfunction "DAT0_P7") (pintype "bidirectional"))
      (node (ref "MISO") (pin "TP") (pinfunction "TP_TP") (pintype "input"))
      (node (ref "R8") (pin "1") (pinfunction "1_1") (pintype "passive"))
      (node (ref "U2") (pin "27") (pinfunction "IO2_27") (pintype "bidirectional"))
      (node (ref "U6") (pin "2") (pinfunction "DO(IO1)_2") (pintype "bidirectional"))
    )
    (net (code "20") (name "MOSI") (class "Default")
      (node (ref "D8") (pin "2") (pinfunction "2_2") (pintype "passive"))
      (node (ref "J1") (pin "P3") (pinfunction "CMD_P3") (pintype "bidirectional"))
      (node (ref "J3") (pin "14") (pinfunction "14_14") (pintype "bidirectional"))
      (node (ref "MOSI") (pin "TP") (pinfunction "TP_TP") (pintype "input"))
      (node (ref "R7") (pin "1") (pinfunction "1_1") (pintype "passive"))
      (node (ref "U2") (pin "7") (pinfunction "IO7_7") (pintype "bidirectional"))
      (node (ref "U6") (pin "5") (pinfunction "DI(IO0)_5") (pintype "bidirectional"))
    )
    (net (code "21") (name "Net-(CHG_LED-PadC)") (class "Default")
      (node (ref "CHG_LED") (pin "C") (pinfunction "C_C") (pintype "passive"))
      (node (ref "R1_BAT") (pin "1") (pinfunction "1_1") (pintype "passive"))
    )
    (net (code "22") (name "Net-(D2-CATHODE)") (class "Default")
      (node (ref "C1_BAT1") (pin "1") (pinfunction "1_1") (pintype "passive"))
      (node (ref "D2") (pin "1") (pinfunction "CATHODE_1") (pintype "bidirectional"))
      (node (ref "IC1") (pin "1") (pinfunction "VIN_1") (pintype "bidirectional"))
      (node (ref "IC1") (pin "3") (pinfunction "CE_3") (pintype "bidirectional"))
      (node (ref "Q1") (pin "2") (pinfunction "S_2") (pintype "bidirectional"))
    )
    (net (code "23") (name "Net-(D3-K)") (class "Default")
      (node (ref "C4") (pin "1") (pinfunction "1_1") (pintype "passive"))
      (node (ref "D3") (pin "1") (pinfunction "K_1") (pintype "bidirectional"))
      (node (ref "D4") (pin "2") (pinfunction "A_2") (pintype "bidirectional"))
    )
    (net (code "24") (name "Net-(D7-CATHODE)") (class "Default")
      (node (ref "D7") (pin "1") (pinfunction "CATHODE_1") (pintype "bidirectional"))
      (node (ref "R_CAPACITOR") (pin "1") (pinfunction "1_1") (pintype "passive"))
    )
    (net (code "25") (name "Net-(EPD_C1-Pad1)") (class "Default")
      (node (ref "EPD_C1") (pin "1") (pinfunction "1_1") (pintype "passive"))
      (node (ref "J3") (pin "4") (pinfunction "4_4") (pintype "bidirectional"))
    )
    (net (code "26") (name "Net-(EPD_C2-Pad1)") (class "Default")
      (node (ref "EPD_C2") (pin "1") (pinfunction "1_1") (pintype "passive"))
      (node (ref "J3") (pin "5") (pinfunction "5_5") (pintype "bidirectional"))
    )
    (net (code "27") (name "Net-(EPD_C5-Pad2)") (class "Default")
      (node (ref "EPD_C5") (pin "2") (pinfunction "2_2") (pintype "passive"))
      (node (ref "J3") (pin "15") (pinfunction "15_15") (pintype "bidirectional"))
    )
    (net (code "28") (name "Net-(EPD_C6-Pad1)") (class "Default")
      (node (ref "EPD_C6") (pin "1") (pinfunction "1_1") (pintype "passive"))
      (node (ref "J3") (pin "18") (pinfunction "18_18") (pintype "bidirectional"))
    )
    (net (code "29") (name "Net-(EPD_C7-Pad1)") (class "Default")
      (node (ref "EPD_C7") (pin "1") (pinfunction "1_1") (pintype "passive"))
      (node (ref "J3") (pin "19") (pinfunction "19_19") (pintype "bidirectional"))
    )
    (net (code "30") (name "Net-(EPD_C8-Pad1)") (class "Default")
      (node (ref "EPD_C8") (pin "1") (pinfunction "1_1") (pintype "passive"))
      (node (ref "J3") (pin "20") (pinfunction "20_20") (pintype "bidirectional"))
    )
    (net (code "31") (name "Net-(EPD_C9-Pad1)") (class "Default")
      (node (ref "EPD_C9") (pin "1") (pinfunction "1_1") (pintype "passive"))
      (node (ref "J3") (pin "21") (pinfunction "21_21") (pintype "bidirectional"))
    )
    (net (code "32") (name "Net-(EPD_C10-Pad1)") (class "Default")
      (node (ref "EPD_C10") (pin "1") (pinfunction "1_1") (pintype "passive"))
      (node (ref "J3") (pin "22") (pinfunction "22_22") (pintype "bidirectional"))
    )
    (net (code "33") (name "Net-(EPD_C11-Pad1)") (class "Default")
      (node (ref "EPD_C11") (pin "1") (pinfunction "1_1") (pintype "passive"))
      (node (ref "J3") (pin "23") (pinfunction "23_23") (pintype "bidirectional"))
    )
    (net (code "34") (name "Net-(EPD_C12-Pad1)") (class "Default")
      (node (ref "EPD_C12") (pin "1") (pinfunction "1_1") (pintype "passive"))
      (node (ref "J3") (pin "24") (pinfunction "24_24") (pintype "bidirectional"))
    )
    (net (code "35") (name "Net-(IC2-CT)") (class "Default")
      (node (ref "C_DELAY") (pin "1") (pinfunction "1_1") (pintype "passive"))
      (node (ref "IC2") (pin "5") (pinfunction "CT_5") (pintype "bidirectional"))
    )
    (net (code "36") (name "Net-(J2-PadA4)") (class "Default")
      (node (ref "J2") (pin "A4") (pinfunction "A4_A4") (pintype "bidirectional"))
      (node (ref "PFMF.050.1") (pin "1") (pinfunction "1_1") (pintype "passive"))
    )
    (net (code "37") (name "Net-(J2-PadA5)") (class "Default")
      (node (ref "J2") (pin "A5") (pinfunction "A5_A5") (pintype "bidirectional"))
      (node (ref "R2-USB1") (pin "2") (pinfunction "2_2") (pintype "passive"))
    )
    (net (code "38") (name "Net-(J2-PadB5)") (class "Default")
      (node (ref "J2") (pin "B5") (pinfunction "B5_B5") (pintype "bidirectional"))
      (node (ref "R2-USB") (pin "1") (pinfunction "1_1") (pintype "passive"))
    )
    (net (code "39") (name "Net-(U1-PROG)") (class "Default")
      (node (ref "R2_BAT") (pin "2") (pinfunction "2_2") (pintype "passive"))
      (node (ref "U1") (pin "5") (pinfunction "PROG_5") (pintype "input"))
    )
    (net (code "40") (name "Net-(U1-STAT)") (class "Default")
      (node (ref "R1_BAT") (pin "2") (pinfunction "2_2") (pintype "passive"))
      (node (ref "U1") (pin "1") (pinfunction "STAT_1") (pintype "output"))
    )
    (net (code "41") (name "PREVGH") (class "Default")
      (node (ref "D5") (pin "1") (pinfunction "K_1") (pintype "bidirectional"))
    )
    (net (code "42") (name "PREVGL") (class "Default")
      (node (ref "D3") (pin "2") (pinfunction "A_2") (pintype "bidirectional"))
    )
    (net (code "43") (name "RESE") (class "Default")
      (node (ref "J3") (pin "3") (pinfunction "3_3") (pintype "bidirectional"))
      (node (ref "Q2") (pin "2") (pinfunction "S_2") (pintype "bidirectional"))
      (node (ref "R3") (pin "2") (pinfunction "2_2") (pintype "passive"))
    )
    (net (code "44") (name "RESE'") (class "Default")
      (node (ref "R2") (pin "2") (pinfunction "2_2") (pintype "passive"))
      (node (ref "R3") (pin "1") (pinfunction "1_1") (pintype "passive"))
      (node (ref "SJ1") (pin "2") (pinfunction "2_2") (pintype "passive"))
    )
    (net (code "45") (name "RESET") (class "Default")
      (node (ref "C5") (pin "1") (pinfunction "1_1") (pintype "passive"))
      (node (ref "IC2") (pin "1") (pinfunction "VOUT_1") (pintype "bidirectional"))
      (node (ref "R14") (pin "1") (pinfunction "1_1") (pintype "passive"))
      (node (ref "RESET_BUTTON") (pin "3") (pinfunction "3_3") (pintype "passive"))
      (node (ref "RESET_BUTTON") (pin "4") (pinfunction "4_4") (pintype "passive"))
      (node (ref "U2") (pin "3") (pinfunction "EN_3") (pintype "input"))
    )
    (net (code "46") (name "RTC_RST") (class "Default")
      (node (ref "U2") (pin "16") (pinfunction "IO18_16") (pintype "bidirectional"))
      (node (ref "U5") (pin "4") (pinfunction "~{RST}_4") (pintype "input"))
    )
    (net (code "47") (name "RX") (class "Default")
      (node (ref "RX") (pin "TP") (pinfunction "TP_TP") (pintype "input"))
      (node (ref "U2") (pin "24") (pinfunction "RXD0/GPIO17_24") (pintype "bidirectional"))
    )
    (net (code "48") (name "SCK") (class "Default")
      (node (ref "D9") (pin "2") (pinfunction "2_2") (pintype "passive"))
      (node (ref "J1") (pin "P5") (pinfunction "CLK_P5") (pintype "bidirectional"))
      (node (ref "J3") (pin "13") (pinfunction "13_13") (pintype "bidirectional"))
      (node (ref "R6") (pin "1") (pinfunction "1_1") (pintype "passive"))
      (node (ref "SCK") (pin "TP") (pinfunction "TP_TP") (pintype "input"))
      (node (ref "U2") (pin "6") (pinfunction "IO6_6") (pintype "bidirectional"))
      (node (ref "U6") (pin "6") (pinfunction "CLK_6") (pintype "input"))
    )
    (net (code "49") (name "SCL") (class "Default")
      (node (ref "J4") (pin "4") (pinfunction "4_4") (pintype "passive"))
      (node (ref "R2-PINH") (pin "1") (pinfunction "1_1") (pintype "passive"))
      (node (ref "U2") (pin "20") (pinfunction "IO22_20") (pintype "bidirectional"))
      (node (ref "U3") (pin "4") (pinfunction "SCK_4") (pintype "input"))
      (node (ref "U4") (pin "7") (pinfunction "SCL_7") (pintype "input"))
      (node (ref "U5") (pin "16") (pinfunction "SCL_16") (pintype "input"))
    )
    (net (code "50") (name "SDA") (class "Default")
      (node (ref "J4") (pin "3") (pinfunction "3_3") (pintype "passive"))
      (node (ref "R1_PINH") (pin "1") (pinfunction "1_1") (pintype "passive"))
      (node (ref "U2") (pin "19") (pinfunction "IO21_19") (pintype "bidirectional"))
      (node (ref "U3") (pin "3") (pinfunction "SDI_3") (pintype "bidirectional"))
      (node (ref "U4") (pin "8") (pinfunction "SDA_8") (pintype "bidirectional"))
      (node (ref "U5") (pin "15") (pinfunction "SDA_15") (pintype "bidirectional"))
    )
    (net (code "51") (name "SRC") (class "Default")
      (node (ref "C4") (pin "2") (pinfunction "2_2") (pintype "passive"))
      (node (ref "D5") (pin "2") (pinfunction "A_2") (pintype "bidirectional"))
      (node (ref "L1") (pin "1") (pinfunction "1_1") (pintype "passive"))
      (node (ref "Q2") (pin "3") (pinfunction "D_3") (pintype "bidirectional"))
    )
    (net (code "52") (name "SS_SD") (class "Default")
      (node (ref "D12") (pin "2") (pinfunction "2_2") (pintype "passive"))
      (node (ref "J1") (pin "P2") (pinfunction "CD/DAT3_P2") (pintype "bidirectional"))
      (node (ref "R22") (pin "1") (pinfunction "1_1") (pintype "passive"))
      (node (ref "U2") (pin "4") (pinfunction "IO4_4") (pintype "bidirectional"))
    )
    (net (code "53") (name "TX") (class "Default")
      (node (ref "TX") (pin "TP") (pinfunction "TP_TP") (pintype "input"))
      (node (ref "U2") (pin "25") (pinfunction "TXD0/GPIO16_25") (pintype "bidirectional"))
    )
    (net (code "54") (name "USB_D+") (class "Default")
      (node (ref "D1") (pin "4") (pinfunction "I/O2_2_4") (pintype "bidirectional"))
      (node (ref "U2") (pin "14") (pinfunction "IO13_14") (pintype "bidirectional"))
    )
    (net (code "55") (name "USB_D-") (class "Default")
      (node (ref "D1") (pin "6") (pinfunction "I/O1_2_6") (pintype "bidirectional"))
      (node (ref "U2") (pin "13") (pinfunction "IO12_13") (pintype "bidirectional"))
    )
    (net (code "56") (name "VBAT") (class "Default")
      (node (ref "C2_BAT") (pin "1") (pinfunction "1_1") (pintype "passive"))
      (node (ref "Q1") (pin "3") (pinfunction "D_3") (pintype "bidirectional"))
      (node (ref "U1") (pin "3") (pinfunction "VBAT_3") (pintype "power_in"))
      (node (ref "U4") (pin "2") (pinfunction "CELL_2") (pintype "power_in"))
      (node (ref "U4") (pin "3") (pinfunction "VDD_3") (pintype "power_in"))
      (node (ref "VBAT") (pin "TP") (pinfunction "TP_TP") (pintype "input"))
    )
    (net (code "57") (name "VBUS") (class "Default")
      (node (ref "C1_BAT") (pin "1") (pinfunction "1_1") (pintype "passive"))
      (node (ref "C4_USB") (pin "1") (pinfunction "1_1") (pintype "passive"))
      (node (ref "C5_USB") (pin "1") (pinfunction "1_1") (pintype "passive"))
      (node (ref "CHG_LED") (pin "A") (pinfunction "A_A") (pintype "passive"))
      (node (ref "D1") (pin "2") (pinfunction "GND_2") (pintype "bidirectional"))
      (node (ref "D2") (pin "2") (pinfunction "ANODE_2") (pintype "bidirectional"))
      (node (ref "PFMF.050.1") (pin "2") (pinfunction "2_2") (pintype "passive"))
      (node (ref "Q1") (pin "1") (pinfunction "G_1") (pintype "bidirectional"))
      (node (ref "R1_PWRUSB") (pin "2") (pinfunction "2_2") (pintype "passive"))
      (node (ref "U1") (pin "4") (pinfunction "VIN_4") (pintype "power_in"))
      (node (ref "VBUS") (pin "TP") (pinfunction "TP_TP") (pintype "input"))
    )
    (net (code "58") (name "VRTC") (class "Default")
      (node (ref "C8") (pin "1") (pinfunction "1_1") (pintype "passive"))
      (node (ref "C9") (pin "1") (pinfunction "1_1") (pintype "passive"))
      (node (ref "R_CAPACITOR") (pin "2") (pinfunction "2_2") (pintype "passive"))
      (node (ref "U5") (pin "14") (pinfunction "VBAT_14") (pintype "power_in"))
    )
    (net (code "59") (name "VUSB") (class "Default")
      (node (ref "J2") (pin "A9") (pinfunction "A9_A9") (pintype "bidirectional"))
      (node (ref "J2") (pin "B4") (pinfunction "B4_B4") (pintype "bidirectional"))
      (node (ref "J2") (pin "B9") (pinfunction "B9_B9") (pintype "bidirectional"))
    )
    (net (code "60") (name "unconnected-(IC1-NC-Pad4)") (class "Default")
      (node (ref "IC1") (pin "4") (pinfunction "NC_4") (pintype "no_connect"))
    )
    (net (code "61") (name "unconnected-(IC2-NC-Pad4)") (class "Default")
      (node (ref "IC2") (pin "4") (pinfunction "NC_4") (pintype "no_connect"))
    )
    (net (code "62") (name "unconnected-(J1-DAT1-PadP8)") (class "Default")
      (node (ref "J1") (pin "P8") (pinfunction "DAT1_P8") (pintype "bidirectional"))
    )
    (net (code "63") (name "unconnected-(J1-DAT2-PadP1)") (class "Default")
      (node (ref "J1") (pin "P1") (pinfunction "DAT2_P1") (pintype "bidirectional"))
    )
    (net (code "64") (name "unconnected-(J1-DETECTION_1-PadS1)") (class "Default")
      (node (ref "J1") (pin "S1") (pinfunction "DETECTION_1_S1") (pintype "bidirectional"))
    )
    (net (code "65") (name "unconnected-(J1-DETECTION_2-PadS2)") (class "Default")
      (node (ref "J1") (pin "S2") (pinfunction "DETECTION_2_S2") (pintype "bidirectional"))
    )
    (net (code "66") (name "unconnected-(J2-PadA8)") (class "Default")
      (node (ref "J2") (pin "A8") (pinfunction "A8_A8") (pintype "bidirectional"))
    )
    (net (code "67") (name "unconnected-(J2-PadB8)") (class "Default")
      (node (ref "J2") (pin "B8") (pinfunction "B8_B8") (pintype "bidirectional"))
    )
    (net (code "68") (name "unconnected-(J3-Pad1)") (class "Default")
      (node (ref "J3") (pin "1") (pinfunction "1_1") (pintype "bidirectional"))
    )
    (net (code "69") (name "unconnected-(J3-Pad6)") (class "Default")
      (node (ref "J3") (pin "6") (pinfunction "6_6") (pintype "bidirectional"))
    )
    (net (code "70") (name "unconnected-(J3-Pad7)") (class "Default")
      (node (ref "J3") (pin "7") (pinfunction "7_7") (pintype "bidirectional"))
    )
    (net (code "71") (name "unconnected-(U2-NC-Pad22)") (class "Default")
      (node (ref "U2") (pin "22") (pinfunction "NC_22") (pintype "no_connect"))
    )
    (net (code "72") (name "unconnected-(U4-~{ALERT}-Pad5)") (class "Default")
      (node (ref "U4") (pin "5") (pinfunction "~{ALERT}_5") (pintype "output"))
    )
  )
)
